# schematic.net
KiCad netlist of a schematic drawn in Altium Designer
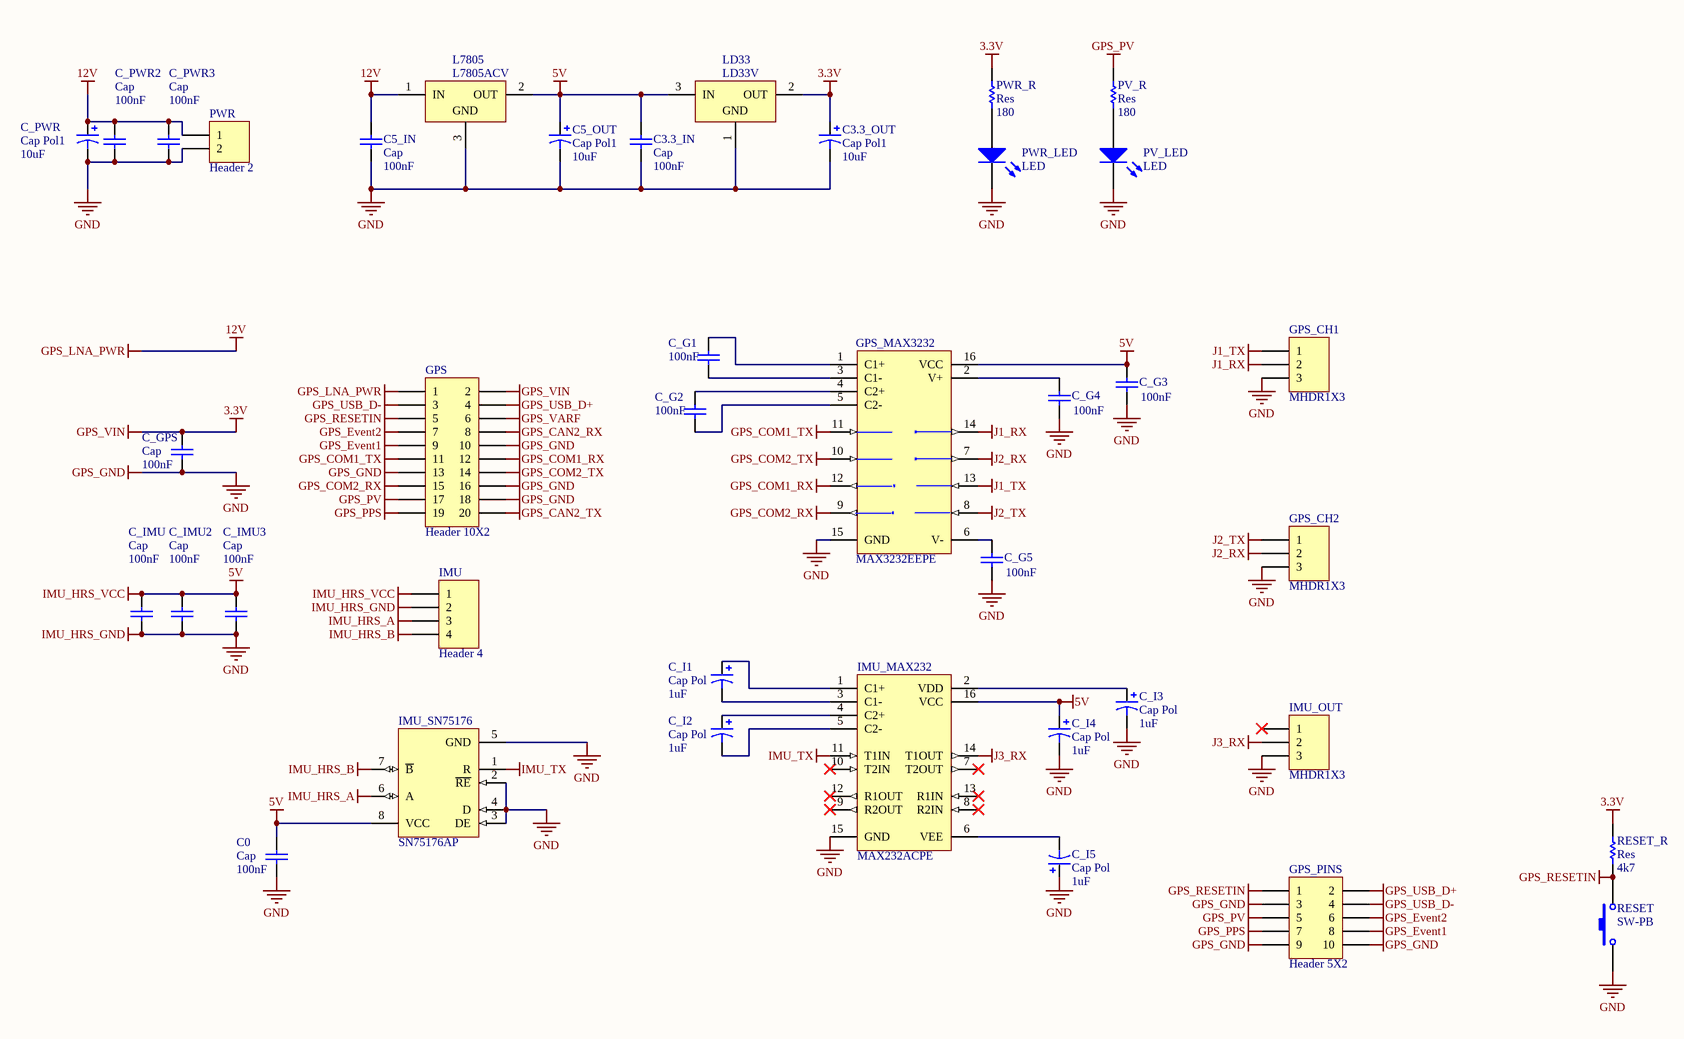
[diagram p0: schematic.SchDoc]

(export (version "E")
  (design (tool "Eeschema 10.0.6"))
  (components
    (comp (ref "C0")
      (value "Cap")
      (footprint "C_NANO_HOLES")
      (description "Capacitor")
      (fields (field (name "ALTIUM_VALUE") "100nF") (field (name "PUBLISHER") "Altium Limited"))
      (libsource (lib "Miscellaneous Devices") (part "Cap"))
    )
    (comp (ref "C3.3_IN")
      (value "Cap")
      (footprint "C_NANO_HOLES")
      (description "Capacitor")
      (fields (field (name "ALTIUM_VALUE") "100nF") (field (name "PUBLISHER") "Altium Limited"))
      (libsource (lib "Miscellaneous Devices") (part "Cap"))
    )
    (comp (ref "C3.3_OUT")
      (value "Cap Pol1")
      (footprint "B")
      (description "Polarized Capacitor (Radial)")
      (fields (field (name "ALTIUM_VALUE") "10uF") (field (name "PUBLISHER") "Altium Limited"))
      (libsource (lib "Miscellaneous Devices") (part "Cap Pol1"))
    )
    (comp (ref "C5_IN")
      (value "Cap")
      (footprint "C_NANO_HOLES")
      (description "Capacitor")
      (fields (field (name "ALTIUM_VALUE") "100nF") (field (name "PUBLISHER") "Altium Limited"))
      (libsource (lib "Miscellaneous Devices") (part "Cap"))
    )
    (comp (ref "C5_OUT")
      (value "Cap Pol1")
      (footprint "B")
      (description "Polarized Capacitor (Radial)")
      (fields (field (name "ALTIUM_VALUE") "10uF") (field (name "PUBLISHER") "Altium Limited"))
      (libsource (lib "Miscellaneous Devices") (part "Cap Pol1"))
    )
    (comp (ref "C_G1")
      (value "100nF")
      (footprint "C_NANO_HOLES")
      (description "Capacitor")
      (fields (field (name "PUBLISHER") "Altium Limited"))
      (libsource (lib "Miscellaneous Devices") (part "Cap"))
    )
    (comp (ref "C_G2")
      (value "100nF")
      (footprint "C_NANO_HOLES")
      (description "Capacitor")
      (fields (field (name "PUBLISHER") "Altium Limited"))
      (libsource (lib "Miscellaneous Devices") (part "Cap"))
    )
    (comp (ref "C_G3")
      (value "100nF")
      (footprint "C_NANO_HOLES")
      (description "Capacitor")
      (fields (field (name "PUBLISHER") "Altium Limited"))
      (libsource (lib "Miscellaneous Devices") (part "Cap"))
    )
    (comp (ref "C_G4")
      (value "100nF")
      (footprint "C_NANO_HOLES")
      (description "Capacitor")
      (fields (field (name "PUBLISHER") "Altium Limited"))
      (libsource (lib "Miscellaneous Devices") (part "Cap"))
    )
    (comp (ref "C_G5")
      (value "100nF")
      (footprint "C_NANO_HOLES")
      (description "Capacitor")
      (fields (field (name "PUBLISHER") "Altium Limited"))
      (libsource (lib "Miscellaneous Devices") (part "Cap"))
    )
    (comp (ref "C_GPS")
      (value "Cap")
      (footprint "C_NANO_HOLES")
      (description "Capacitor")
      (fields (field (name "ALTIUM_VALUE") "100nF") (field (name "PUBLISHER") "Altium Limited"))
      (libsource (lib "Miscellaneous Devices") (part "Cap"))
    )
    (comp (ref "C_I1")
      (value "Cap Pol")
      (footprint "B")
      (description "Polarized Capacitor (Radial)")
      (fields (field (name "ALTIUM_VALUE") "1uF") (field (name "PUBLISHER") "Altium Limited"))
      (libsource (lib "Miscellaneous Devices") (part "Cap Pol1"))
    )
    (comp (ref "C_I2")
      (value "Cap Pol")
      (footprint "B")
      (description "Polarized Capacitor (Radial)")
      (fields (field (name "ALTIUM_VALUE") "1uF") (field (name "PUBLISHER") "Altium Limited"))
      (libsource (lib "Miscellaneous Devices") (part "Cap Pol1"))
    )
    (comp (ref "C_I3")
      (value "Cap Pol")
      (footprint "B")
      (description "Polarized Capacitor (Radial)")
      (fields (field (name "ALTIUM_VALUE") "1uF") (field (name "PUBLISHER") "Altium Limited"))
      (libsource (lib "Miscellaneous Devices") (part "Cap Pol1"))
    )
    (comp (ref "C_I4")
      (value "Cap Pol")
      (footprint "B")
      (description "Polarized Capacitor (Radial)")
      (fields (field (name "ALTIUM_VALUE") "1uF") (field (name "PUBLISHER") "Altium Limited"))
      (libsource (lib "Miscellaneous Devices") (part "Cap Pol1"))
    )
    (comp (ref "C_I5")
      (value "Cap Pol")
      (footprint "B")
      (description "Polarized Capacitor (Radial)")
      (fields (field (name "ALTIUM_VALUE") "1uF") (field (name "PUBLISHER") "Altium Limited"))
      (libsource (lib "Miscellaneous Devices") (part "Cap Pol1"))
    )
    (comp (ref "C_IMU")
      (value "Cap")
      (footprint "C_NANO_HOLES")
      (description "Capacitor")
      (fields (field (name "ALTIUM_VALUE") "100nF") (field (name "PUBLISHER") "Altium Limited"))
      (libsource (lib "Miscellaneous Devices") (part "Cap"))
    )
    (comp (ref "C_IMU2")
      (value "Cap")
      (footprint "C_NANO_HOLES")
      (description "Capacitor")
      (fields (field (name "ALTIUM_VALUE") "100nF") (field (name "PUBLISHER") "Altium Limited"))
      (libsource (lib "Miscellaneous Devices") (part "Cap"))
    )
    (comp (ref "C_IMU3")
      (value "Cap")
      (footprint "C_NANO_HOLES")
      (description "Capacitor")
      (fields (field (name "ALTIUM_VALUE") "100nF") (field (name "PUBLISHER") "Altium Limited"))
      (libsource (lib "Miscellaneous Devices") (part "Cap"))
    )
    (comp (ref "C_PWR")
      (value "Cap Pol1")
      (footprint "B")
      (description "Polarized Capacitor (Radial)")
      (fields (field (name "ALTIUM_VALUE") "10uF") (field (name "PUBLISHER") "Altium Limited"))
      (libsource (lib "Miscellaneous Devices") (part "Cap Pol1"))
    )
    (comp (ref "C_PWR2")
      (value "Cap")
      (footprint "C_NANO_HOLES")
      (description "Capacitor")
      (fields (field (name "ALTIUM_VALUE") "100nF") (field (name "PUBLISHER") "Altium Limited"))
      (libsource (lib "Miscellaneous Devices") (part "Cap"))
    )
    (comp (ref "C_PWR3")
      (value "Cap")
      (footprint "C_NANO_HOLES")
      (description "Capacitor")
      (fields (field (name "ALTIUM_VALUE") "100nF") (field (name "PUBLISHER") "Altium Limited"))
      (libsource (lib "Miscellaneous Devices") (part "Cap"))
    )
    (comp (ref "GPS")
      (value "Header 10X2")
      (footprint "HDR2X10")
      (description "Header, 10-Pin, Dual row")
      (fields (field (name "PUBLISHER") "Altium Limited"))
      (libsource (lib "Miscellaneous Connectors") (part "Header 10X2"))
    )
    (comp (ref "GPS_CH1")
      (value "MHDR1X3")
      (footprint "HDR1X3")
      (description "Header, 3-Pin")
      (fields (field (name "PUBLISHER") "Altium Limited"))
      (libsource (lib "Miscellaneous Connectors") (part "MHDR1X3"))
    )
    (comp (ref "GPS_CH2")
      (value "MHDR1X3")
      (footprint "HDR1X3")
      (description "Header, 3-Pin")
      (fields (field (name "PUBLISHER") "Altium Limited"))
      (libsource (lib "Miscellaneous Connectors") (part "MHDR1X3"))
    )
    (comp (ref "GPS_MAX3232")
      (value "MAX3232EEPE")
      (footprint "Maxim Footprints:PE16")
      (description "±15kV ESD-Protected, 3.0V to 5.5V, Low-Power, up to 250kbps, True RS-232 Transceiver")
      (fields (field (name "PUBLISHER") "Altium Limited"))
      (libsource (lib "Maxim Communication Transceiver") (part "MAX3232EEPE"))
    )
    (comp (ref "GPS_PINS")
      (value "Header 5X2")
      (footprint "HDR2X5")
      (description "Header, 5-Pin, Dual row")
      (fields (field (name "PUBLISHER") "Altium Limited"))
      (libsource (lib "Miscellaneous Connectors") (part "Header 5X2"))
    )
    (comp (ref "IMU")
      (value "Header 4")
      (footprint "HDR1X4")
      (description "Header, 4-Pin")
      (fields (field (name "PUBLISHER") "Altium Limited"))
      (libsource (lib "Miscellaneous Connectors") (part "Header 4"))
    )
    (comp (ref "IMU_MAX232")
      (value "MAX232ACPE")
      (footprint "PE16A")
      (description "+5V Powered, Multi-Channel RS-232 Driver/Receiver")
      (fields (field (name "PUBLISHER") "Altium Limited"))
      (libsource (lib "Maxim Communication Transceiver") (part "MAX232ACPE"))
    )
    (comp (ref "IMU_OUT")
      (value "MHDR1X3")
      (footprint "HDR1X3")
      (description "Header, 3-Pin")
      (fields (field (name "PUBLISHER") "Altium Limited"))
      (libsource (lib "Miscellaneous Connectors") (part "MHDR1X3"))
    )
    (comp (ref "IMU_SN75176")
      (value "SN75176AP")
      (footprint "P008")
      (description "Differential Bus Transceiver")
      (fields (field (name "PUBLISHER") "Altium Limited"))
      (libsource (lib "TI Interface Line Transceiver") (part "SN75176AP"))
    )
    (comp (ref "L7805")
      (value "L7805ACV")
      (footprint "TO220ABN")
      (description "Precision 1A Regulator")
      (fields (field (name "PUBLISHER") "Altium Limited"))
      (libsource (lib "ST Power Mgt Voltage Regulator") (part "L7805ACV"))
    )
    (comp (ref "LD33")
      (value "LD33V")
      (footprint "T03B")
      (description "800mA Low-Dropout Linear Regulator")
      (fields
        (field (name "PARTNUMBER") "LM1117T-3.3")
        (field (name "MANUFACTURER") "National Semiconductor")
        (field (name "PUBLISHER") "Altium Limited")
      )
      (libsource (lib "NSC LDO") (part "LM1117T-3.3"))
    )
    (comp (ref "PV_LED")
      (value "LED")
      (footprint "B")
      (description "Typical INFRARED GaAs LED")
      (fields (field (name "PUBLISHER") "Altium Limited"))
      (libsource (lib "Miscellaneous Devices") (part "LED0"))
    )
    (comp (ref "PV_R")
      (value "Res")
      (footprint "AXIAL-0.3")
      (description "Resistor")
      (fields (field (name "ALTIUM_VALUE") "180") (field (name "PUBLISHER") "Altium Limited"))
      (libsource (lib "Miscellaneous Devices") (part "Res1"))
    )
    (comp (ref "PWR")
      (value "Header 2")
      (footprint "HDR1X2")
      (description "Header, 2-Pin")
      (fields (field (name "PUBLISHER") "Altium Limited"))
      (libsource (lib "Miscellaneous Connectors") (part "Header 2"))
    )
    (comp (ref "PWR_LED")
      (value "LED")
      (footprint "B")
      (description "Typical INFRARED GaAs LED")
      (fields (field (name "PUBLISHER") "Altium Limited"))
      (libsource (lib "Miscellaneous Devices") (part "LED0"))
    )
    (comp (ref "PWR_R")
      (value "Res")
      (footprint "AXIAL-0.3")
      (description "Resistor")
      (fields (field (name "ALTIUM_VALUE") "180") (field (name "PUBLISHER") "Altium Limited"))
      (libsource (lib "Miscellaneous Devices") (part "Res1"))
    )
    (comp (ref "RESET")
      (value "SW-PB")
      (footprint "PUSHBUTTON")
      (description "Switch")
      (fields (field (name "PUBLISHER") "Altium Limited"))
      (libsource (lib "Miscellaneous Devices") (part "SW-PB"))
    )
    (comp (ref "RESET_R")
      (value "Res")
      (footprint "AXIAL-0.3")
      (description "Resistor")
      (fields (field (name "ALTIUM_VALUE") "4k7") (field (name "PUBLISHER") "Altium Limited"))
      (libsource (lib "Miscellaneous Devices") (part "Res1"))
    )
  )
  (nets
    (net (code "1") (name "3.3V") (class "Default")
      (node (ref "C3.3_OUT") (pin "1") (pinfunction "1_1") (pintype "passive"))
      (node (ref "C_GPS") (pin "2") (pinfunction "2_2") (pintype "passive"))
      (node (ref "GPS") (pin "2") (pinfunction "2_2") (pintype "passive"))
      (node (ref "LD33") (pin "2") (pinfunction "OUT_2") (pintype "power_in"))
      (node (ref "PWR_R") (pin "2") (pinfunction "2_2") (pintype "passive"))
      (node (ref "RESET_R") (pin "2") (pinfunction "2_2") (pintype "passive"))
    )
    (net (code "2") (name "5V") (class "Default")
      (node (ref "C0") (pin "2") (pinfunction "2_2") (pintype "passive"))
      (node (ref "C3.3_IN") (pin "1") (pinfunction "1_1") (pintype "passive"))
      (node (ref "C5_OUT") (pin "1") (pinfunction "1_1") (pintype "passive"))
      (node (ref "C_G3") (pin "2") (pinfunction "2_2") (pintype "passive"))
      (node (ref "C_I4") (pin "1") (pinfunction "1_1") (pintype "passive"))
      (node (ref "C_IMU") (pin "2") (pinfunction "2_2") (pintype "passive"))
      (node (ref "C_IMU2") (pin "2") (pinfunction "2_2") (pintype "passive"))
      (node (ref "C_IMU3") (pin "2") (pinfunction "2_2") (pintype "passive"))
      (node (ref "GPS_MAX3232") (pin "16") (pinfunction "VCC_16") (pintype "power_in"))
      (node (ref "IMU") (pin "1") (pinfunction "1_1") (pintype "passive"))
      (node (ref "IMU_MAX232") (pin "16") (pinfunction "VCC_16") (pintype "power_in"))
      (node (ref "IMU_SN75176") (pin "8") (pinfunction "VCC_8") (pintype "power_in"))
      (node (ref "L7805") (pin "2") (pinfunction "OUT_2") (pintype "power_in"))
      (node (ref "LD33") (pin "3") (pinfunction "IN_3") (pintype "power_in"))
    )
    (net (code "3") (name "12V") (class "Default")
      (node (ref "C5_IN") (pin "1") (pinfunction "1_1") (pintype "passive"))
      (node (ref "C_PWR") (pin "1") (pinfunction "1_1") (pintype "passive"))
      (node (ref "C_PWR2") (pin "2") (pinfunction "2_2") (pintype "passive"))
      (node (ref "C_PWR3") (pin "2") (pinfunction "2_2") (pintype "passive"))
      (node (ref "GPS") (pin "1") (pinfunction "1_1") (pintype "passive"))
      (node (ref "L7805") (pin "1") (pinfunction "IN_1") (pintype "power_in"))
      (node (ref "PWR") (pin "1") (pinfunction "1_1") (pintype "passive"))
    )
    (net (code "4") (name "GND") (class "Default")
      (node (ref "C0") (pin "1") (pinfunction "1_1") (pintype "passive"))
      (node (ref "C3.3_IN") (pin "2") (pinfunction "2_2") (pintype "passive"))
      (node (ref "C3.3_OUT") (pin "2") (pinfunction "2_2") (pintype "passive"))
      (node (ref "C5_IN") (pin "2") (pinfunction "2_2") (pintype "passive"))
      (node (ref "C5_OUT") (pin "2") (pinfunction "2_2") (pintype "passive"))
      (node (ref "C_G3") (pin "1") (pinfunction "1_1") (pintype "passive"))
      (node (ref "C_G4") (pin "1") (pinfunction "1_1") (pintype "passive"))
      (node (ref "C_G5") (pin "1") (pinfunction "1_1") (pintype "passive"))
      (node (ref "C_GPS") (pin "1") (pinfunction "1_1") (pintype "passive"))
      (node (ref "C_I3") (pin "2") (pinfunction "2_2") (pintype "passive"))
      (node (ref "C_I4") (pin "2") (pinfunction "2_2") (pintype "passive"))
      (node (ref "C_I5") (pin "1") (pinfunction "1_1") (pintype "passive"))
      (node (ref "C_IMU") (pin "1") (pinfunction "1_1") (pintype "passive"))
      (node (ref "C_IMU2") (pin "1") (pinfunction "1_1") (pintype "passive"))
      (node (ref "C_IMU3") (pin "1") (pinfunction "1_1") (pintype "passive"))
      (node (ref "C_PWR") (pin "2") (pinfunction "2_2") (pintype "passive"))
      (node (ref "C_PWR2") (pin "1") (pinfunction "1_1") (pintype "passive"))
      (node (ref "C_PWR3") (pin "1") (pinfunction "1_1") (pintype "passive"))
      (node (ref "GPS") (pin "10") (pinfunction "10_10") (pintype "passive"))
      (node (ref "GPS") (pin "13") (pinfunction "13_13") (pintype "passive"))
      (node (ref "GPS") (pin "16") (pinfunction "16_16") (pintype "passive"))
      (node (ref "GPS") (pin "18") (pinfunction "18_18") (pintype "passive"))
      (node (ref "GPS_CH1") (pin "3") (pinfunction "3_3") (pintype "passive"))
      (node (ref "GPS_CH2") (pin "3") (pinfunction "3_3") (pintype "passive"))
      (node (ref "GPS_MAX3232") (pin "15") (pinfunction "GND_15") (pintype "power_in"))
      (node (ref "GPS_PINS") (pin "10") (pinfunction "10_10") (pintype "passive"))
      (node (ref "GPS_PINS") (pin "3") (pinfunction "3_3") (pintype "passive"))
      (node (ref "GPS_PINS") (pin "9") (pinfunction "9_9") (pintype "passive"))
      (node (ref "IMU") (pin "2") (pinfunction "2_2") (pintype "passive"))
      (node (ref "IMU_MAX232") (pin "15") (pinfunction "GND_15") (pintype "power_in"))
      (node (ref "IMU_OUT") (pin "3") (pinfunction "3_3") (pintype "passive"))
      (node (ref "IMU_SN75176") (pin "2") (pinfunction "~{RE}_2") (pintype "input"))
      (node (ref "IMU_SN75176") (pin "3") (pinfunction "DE_3") (pintype "input"))
      (node (ref "IMU_SN75176") (pin "4") (pinfunction "D_4") (pintype "input"))
      (node (ref "IMU_SN75176") (pin "5") (pinfunction "GND_5") (pintype "power_in"))
      (node (ref "L7805") (pin "3") (pinfunction "GND_3") (pintype "power_in"))
      (node (ref "LD33") (pin "1") (pinfunction "GND_1") (pintype "power_in"))
      (node (ref "PV_LED") (pin "2") (pinfunction "K_2") (pintype "passive"))
      (node (ref "PWR") (pin "2") (pinfunction "2_2") (pintype "passive"))
      (node (ref "PWR_LED") (pin "2") (pinfunction "K_2") (pintype "passive"))
      (node (ref "RESET") (pin "1") (pinfunction "1_1") (pintype "passive"))
    )
    (net (code "5") (name "GPS_CAN2_RX") (class "Default")
      (node (ref "GPS") (pin "8") (pinfunction "8_8") (pintype "passive"))
    )
    (net (code "6") (name "GPS_CAN2_TX") (class "Default")
      (node (ref "GPS") (pin "20") (pinfunction "20_20") (pintype "passive"))
    )
    (net (code "7") (name "GPS_COM1_RX") (class "Default")
      (node (ref "GPS") (pin "12") (pinfunction "12_12") (pintype "passive"))
      (node (ref "GPS_MAX3232") (pin "12") (pinfunction "R1OUT_12") (pintype "output"))
    )
    (net (code "8") (name "GPS_COM1_TX") (class "Default")
      (node (ref "GPS") (pin "11") (pinfunction "11_11") (pintype "passive"))
      (node (ref "GPS_MAX3232") (pin "11") (pinfunction "T1IN_11") (pintype "input"))
    )
    (net (code "9") (name "GPS_COM2_RX") (class "Default")
      (node (ref "GPS") (pin "15") (pinfunction "15_15") (pintype "passive"))
      (node (ref "GPS_MAX3232") (pin "9") (pinfunction "R2OUT_9") (pintype "output"))
    )
    (net (code "10") (name "GPS_COM2_TX") (class "Default")
      (node (ref "GPS") (pin "14") (pinfunction "14_14") (pintype "passive"))
      (node (ref "GPS_MAX3232") (pin "10") (pinfunction "T2IN_10") (pintype "input"))
    )
    (net (code "11") (name "GPS_Event1") (class "Default")
      (node (ref "GPS") (pin "9") (pinfunction "9_9") (pintype "passive"))
      (node (ref "GPS_PINS") (pin "8") (pinfunction "8_8") (pintype "passive"))
    )
    (net (code "12") (name "GPS_Event2") (class "Default")
      (node (ref "GPS") (pin "7") (pinfunction "7_7") (pintype "passive"))
      (node (ref "GPS_PINS") (pin "6") (pinfunction "6_6") (pintype "passive"))
    )
    (net (code "13") (name "GPS_PPS") (class "Default")
      (node (ref "GPS") (pin "19") (pinfunction "19_19") (pintype "passive"))
      (node (ref "GPS_PINS") (pin "7") (pinfunction "7_7") (pintype "passive"))
    )
    (net (code "14") (name "GPS_PV") (class "Default")
      (node (ref "GPS") (pin "17") (pinfunction "17_17") (pintype "passive"))
      (node (ref "GPS_PINS") (pin "5") (pinfunction "5_5") (pintype "passive"))
      (node (ref "PV_R") (pin "2") (pinfunction "2_2") (pintype "passive"))
    )
    (net (code "15") (name "GPS_RESETIN") (class "Default")
      (node (ref "GPS") (pin "5") (pinfunction "5_5") (pintype "passive"))
      (node (ref "GPS_PINS") (pin "1") (pinfunction "1_1") (pintype "passive"))
      (node (ref "RESET") (pin "2") (pinfunction "2_2") (pintype "passive"))
      (node (ref "RESET_R") (pin "1") (pinfunction "1_1") (pintype "passive"))
    )
    (net (code "16") (name "GPS_USB_D+") (class "Default")
      (node (ref "GPS") (pin "4") (pinfunction "4_4") (pintype "passive"))
      (node (ref "GPS_PINS") (pin "2") (pinfunction "2_2") (pintype "passive"))
    )
    (net (code "17") (name "GPS_USB_D-") (class "Default")
      (node (ref "GPS") (pin "3") (pinfunction "3_3") (pintype "passive"))
      (node (ref "GPS_PINS") (pin "4") (pinfunction "4_4") (pintype "passive"))
    )
    (net (code "18") (name "GPS_VARF") (class "Default")
      (node (ref "GPS") (pin "6") (pinfunction "6_6") (pintype "passive"))
    )
    (net (code "19") (name "IMU_HRS_A") (class "Default")
      (node (ref "IMU") (pin "3") (pinfunction "3_3") (pintype "passive"))
      (node (ref "IMU_SN75176") (pin "6") (pinfunction "A_6") (pintype "bidirectional"))
    )
    (net (code "20") (name "IMU_HRS_B") (class "Default")
      (node (ref "IMU") (pin "4") (pinfunction "4_4") (pintype "passive"))
      (node (ref "IMU_SN75176") (pin "7") (pinfunction "~{B}_7") (pintype "bidirectional"))
    )
    (net (code "21") (name "IMU_TX") (class "Default")
      (node (ref "IMU_MAX232") (pin "11") (pinfunction "T1IN_11") (pintype "input"))
      (node (ref "IMU_SN75176") (pin "1") (pinfunction "R_1") (pintype "tri_state"))
    )
    (net (code "22") (name "J1_RX") (class "Default")
      (node (ref "GPS_CH1") (pin "2") (pinfunction "2_2") (pintype "passive"))
      (node (ref "GPS_MAX3232") (pin "14") (pinfunction "T1OUT_14") (pintype "output"))
    )
    (net (code "23") (name "J1_TX") (class "Default")
      (node (ref "GPS_CH1") (pin "1") (pinfunction "1_1") (pintype "passive"))
      (node (ref "GPS_MAX3232") (pin "13") (pinfunction "R1IN_13") (pintype "input"))
    )
    (net (code "24") (name "J2_RX") (class "Default")
      (node (ref "GPS_CH2") (pin "2") (pinfunction "2_2") (pintype "passive"))
      (node (ref "GPS_MAX3232") (pin "7") (pinfunction "T2OUT_7") (pintype "output"))
    )
    (net (code "25") (name "J2_TX") (class "Default")
      (node (ref "GPS_CH2") (pin "1") (pinfunction "1_1") (pintype "passive"))
      (node (ref "GPS_MAX3232") (pin "8") (pinfunction "R2IN_8") (pintype "input"))
    )
    (net (code "26") (name "J3_RX") (class "Default")
      (node (ref "IMU_MAX232") (pin "14") (pinfunction "T1OUT_14") (pintype "output"))
      (node (ref "IMU_OUT") (pin "2") (pinfunction "2_2") (pintype "passive"))
    )
    (net (code "27") (name "Net-(GPS_MAX3232-C1+)") (class "Default")
      (node (ref "C_G1") (pin "2") (pinfunction "2_2") (pintype "passive"))
      (node (ref "GPS_MAX3232") (pin "1") (pinfunction "C1+_1") (pintype "passive"))
    )
    (net (code "28") (name "Net-(GPS_MAX3232-C1-)") (class "Default")
      (node (ref "C_G1") (pin "1") (pinfunction "1_1") (pintype "passive"))
      (node (ref "GPS_MAX3232") (pin "3") (pinfunction "C1-_3") (pintype "passive"))
    )
    (net (code "29") (name "Net-(GPS_MAX3232-C2+)") (class "Default")
      (node (ref "C_G2") (pin "2") (pinfunction "2_2") (pintype "passive"))
      (node (ref "GPS_MAX3232") (pin "4") (pinfunction "C2+_4") (pintype "passive"))
    )
    (net (code "30") (name "Net-(GPS_MAX3232-C2-)") (class "Default")
      (node (ref "C_G2") (pin "1") (pinfunction "1_1") (pintype "passive"))
      (node (ref "GPS_MAX3232") (pin "5") (pinfunction "C2-_5") (pintype "passive"))
    )
    (net (code "31") (name "Net-(GPS_MAX3232-V+)") (class "Default")
      (node (ref "C_G4") (pin "2") (pinfunction "2_2") (pintype "passive"))
      (node (ref "GPS_MAX3232") (pin "2") (pinfunction "V+_2") (pintype "power_in"))
    )
    (net (code "32") (name "Net-(GPS_MAX3232-V-)") (class "Default")
      (node (ref "C_G5") (pin "2") (pinfunction "2_2") (pintype "passive"))
      (node (ref "GPS_MAX3232") (pin "6") (pinfunction "V-_6") (pintype "power_in"))
    )
    (net (code "33") (name "Net-(IMU_MAX232-C1+)") (class "Default")
      (node (ref "C_I1") (pin "1") (pinfunction "1_1") (pintype "passive"))
      (node (ref "IMU_MAX232") (pin "1") (pinfunction "C1+_1") (pintype "passive"))
    )
    (net (code "34") (name "Net-(IMU_MAX232-C1-)") (class "Default")
      (node (ref "C_I1") (pin "2") (pinfunction "2_2") (pintype "passive"))
      (node (ref "IMU_MAX232") (pin "3") (pinfunction "C1-_3") (pintype "passive"))
    )
    (net (code "35") (name "Net-(IMU_MAX232-C2+)") (class "Default")
      (node (ref "C_I2") (pin "1") (pinfunction "1_1") (pintype "passive"))
      (node (ref "IMU_MAX232") (pin "4") (pinfunction "C2+_4") (pintype "passive"))
    )
    (net (code "36") (name "Net-(IMU_MAX232-C2-)") (class "Default")
      (node (ref "C_I2") (pin "2") (pinfunction "2_2") (pintype "passive"))
      (node (ref "IMU_MAX232") (pin "5") (pinfunction "C2-_5") (pintype "passive"))
    )
    (net (code "37") (name "Net-(IMU_MAX232-VDD)") (class "Default")
      (node (ref "C_I3") (pin "1") (pinfunction "1_1") (pintype "passive"))
      (node (ref "IMU_MAX232") (pin "2") (pinfunction "VDD_2") (pintype "power_in"))
    )
    (net (code "38") (name "Net-(IMU_MAX232-VEE)") (class "Default")
      (node (ref "C_I5") (pin "2") (pinfunction "2_2") (pintype "passive"))
      (node (ref "IMU_MAX232") (pin "6") (pinfunction "VEE_6") (pintype "power_in"))
    )
    (net (code "39") (name "Net-(PV_LED-A)") (class "Default")
      (node (ref "PV_LED") (pin "1") (pinfunction "A_1") (pintype "passive"))
      (node (ref "PV_R") (pin "1") (pinfunction "1_1") (pintype "passive"))
    )
    (net (code "40") (name "Net-(PWR_LED-A)") (class "Default")
      (node (ref "PWR_LED") (pin "1") (pinfunction "A_1") (pintype "passive"))
      (node (ref "PWR_R") (pin "1") (pinfunction "1_1") (pintype "passive"))
    )
    (net (code "41") (name "unconnected-(IMU_MAX232-R1IN-Pad13)") (class "Default")
      (node (ref "IMU_MAX232") (pin "13") (pinfunction "R1IN_13") (pintype "input+no_connect"))
    )
    (net (code "42") (name "unconnected-(IMU_MAX232-R1OUT-Pad12)") (class "Default")
      (node (ref "IMU_MAX232") (pin "12") (pinfunction "R1OUT_12") (pintype "output+no_connect"))
    )
    (net (code "43") (name "unconnected-(IMU_MAX232-R2IN-Pad8)") (class "Default")
      (node (ref "IMU_MAX232") (pin "8") (pinfunction "R2IN_8") (pintype "input+no_connect"))
    )
    (net (code "44") (name "unconnected-(IMU_MAX232-R2OUT-Pad9)") (class "Default")
      (node (ref "IMU_MAX232") (pin "9") (pinfunction "R2OUT_9") (pintype "output+no_connect"))
    )
    (net (code "45") (name "unconnected-(IMU_MAX232-T2IN-Pad10)") (class "Default")
      (node (ref "IMU_MAX232") (pin "10") (pinfunction "T2IN_10") (pintype "input+no_connect"))
    )
    (net (code "46") (name "unconnected-(IMU_MAX232-T2OUT-Pad7)") (class "Default")
      (node (ref "IMU_MAX232") (pin "7") (pinfunction "T2OUT_7") (pintype "output+no_connect"))
    )
    (net (code "47") (name "unconnected-(IMU_OUT-Pad1)") (class "Default")
      (node (ref "IMU_OUT") (pin "1") (pinfunction "1_1") (pintype "passive+no_connect"))
    )
  )
)
